# Schematic_Ej3_Amp_Instrumentacion.net
KiCad netlist of a schematic drawn in Altium Designer
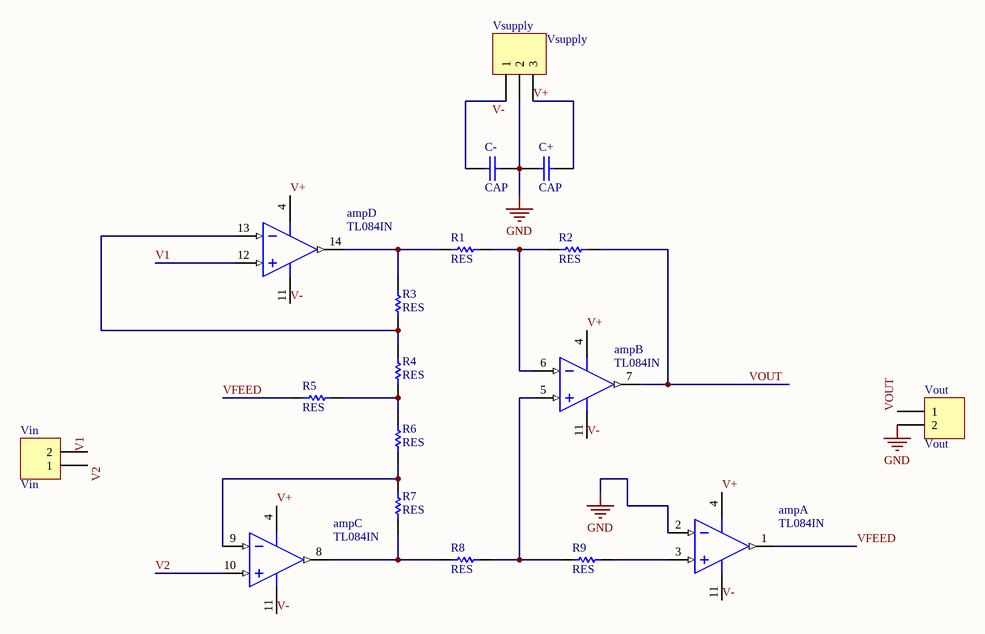
[diagram p0: Schematic_Ej3_Amp_Instrumentacion.SchDoc]

(export (version "E")
  (design (tool "Eeschema 10.0.6"))
  (components
    (comp (ref "amp")
      (value "TL084IN")
      (footprint "TI-N14")
      (description "JFET-Input Operational Amplifier, 7 to 36 V, -40 to 85 degC, 14-pin DIP (N14), Pb-Free (RoHS)")
      (fields (field (name "MANUFACTURER") "Texas Instruments"))
      (libsource (lib "TI Amplifiers and Linear Operational Amplifier General Purpose") (part "TL084IN"))
    )
    (comp (ref "C+") (value "CAP") (footprint "CAP200") (libsource (lib "LIBEBAL") (part "CAP")))
    (comp (ref "C-") (value "CAP") (footprint "CAP200") (libsource (lib "LIBEBAL") (part "CAP")))
    (comp (ref "R1") (value "RES") (footprint "0805") (libsource (lib "LIBEBAL") (part "RES")))
    (comp (ref "R2") (value "RES") (footprint "0805") (libsource (lib "LIBEBAL") (part "RES")))
    (comp (ref "R3") (value "RES") (footprint "0805") (libsource (lib "LIBEBAL") (part "RES")))
    (comp (ref "R4") (value "RES") (footprint "0805") (libsource (lib "LIBEBAL") (part "RES")))
    (comp (ref "R5") (value "RES") (footprint "0805") (libsource (lib "LIBEBAL") (part "RES")))
    (comp (ref "R6") (value "RES") (footprint "0805") (libsource (lib "LIBEBAL") (part "RES")))
    (comp (ref "R7") (value "RES") (footprint "0805") (libsource (lib "LIBEBAL") (part "RES")))
    (comp (ref "R8") (value "RES") (footprint "0805") (libsource (lib "LIBEBAL") (part "RES")))
    (comp (ref "R9") (value "RES") (footprint "0805") (libsource (lib "LIBEBAL") (part "RES")))
    (comp (ref "Vin")
      (value "Vin")
      (footprint "HDR1X2")
      (description "Header, 2-Pin")
      (fields (field (name "PUBLISHER") "Altium Limited"))
      (libsource (lib "") (part "Header 2_1"))
    )
    (comp (ref "Vout")
      (value "Vout")
      (footprint "HDR1X2")
      (description "Header, 2-Pin")
      (fields (field (name "PUBLISHER") "Altium Limited"))
      (libsource (lib "Miscellaneous Connectors") (part "Header 2"))
    )
    (comp (ref "Vsupply")
      (value "Vsupply")
      (footprint "HDR1X3")
      (description "Header, 3-Pin")
      (fields (field (name "PUBLISHER") "Altium Limited"))
      (libsource (lib "Miscellaneous Connectors") (part "Header 3"))
    )
  )
  (nets
    (net (code "1") (name "/V+") (class "Default")
      (node (ref "C+") (pin "2") (pinfunction "2_2") (pintype "passive"))
      (node (ref "Vsupply") (pin "3") (pinfunction "3_3") (pintype "passive"))
      (node (ref "amp") (pin "4") (pinfunction "VCC+_4") (pintype "power_in"))
    )
    (net (code "2") (name "/V-") (class "Default")
      (node (ref "C-") (pin "1") (pinfunction "1_1") (pintype "passive"))
      (node (ref "Vsupply") (pin "1") (pinfunction "1_1") (pintype "passive"))
      (node (ref "amp") (pin "11") (pinfunction "VCC-_11") (pintype "power_in"))
    )
    (net (code "3") (name "/V1") (class "Default")
      (node (ref "Vin") (pin "2") (pinfunction "2_2") (pintype "passive"))
      (node (ref "amp") (pin "12") (pinfunction "IN4+_12") (pintype "input"))
    )
    (net (code "4") (name "/V2") (class "Default")
      (node (ref "Vin") (pin "1") (pinfunction "1_1") (pintype "passive"))
      (node (ref "amp") (pin "10") (pinfunction "IN3+_10") (pintype "input"))
    )
    (net (code "5") (name "/VFEED") (class "Default")
      (node (ref "R5") (pin "1") (pinfunction "1_1") (pintype "passive"))
      (node (ref "amp") (pin "1") (pinfunction "OUT1_1") (pintype "output"))
    )
    (net (code "6") (name "/VOUT") (class "Default")
      (node (ref "R2") (pin "1") (pinfunction "1_1") (pintype "passive"))
      (node (ref "Vout") (pin "1") (pinfunction "1_1") (pintype "passive"))
      (node (ref "amp") (pin "7") (pinfunction "OUT2_7") (pintype "output"))
    )
    (net (code "7") (name "GND") (class "Default")
      (node (ref "C+") (pin "1") (pinfunction "1_1") (pintype "passive"))
      (node (ref "C-") (pin "2") (pinfunction "2_2") (pintype "passive"))
      (node (ref "Vout") (pin "2") (pinfunction "2_2") (pintype "passive"))
      (node (ref "Vsupply") (pin "2") (pinfunction "2_2") (pintype "passive"))
      (node (ref "amp") (pin "2") (pinfunction "IN1-_2") (pintype "input"))
    )
    (net (code "8") (name "Net-(R4-Pad1)") (class "Default")
      (node (ref "R4") (pin "1") (pinfunction "1_1") (pintype "passive"))
      (node (ref "R5") (pin "2") (pinfunction "2_2") (pintype "passive"))
      (node (ref "R6") (pin "1") (pinfunction "1_1") (pintype "passive"))
    )
    (net (code "9") (name "Net-(ampA-IN1+)") (class "Default")
      (node (ref "R9") (pin "2") (pinfunction "2_2") (pintype "passive"))
      (node (ref "amp") (pin "3") (pinfunction "IN1+_3") (pintype "input"))
    )
    (net (code "10") (name "Net-(ampB-IN2+)") (class "Default")
      (node (ref "R8") (pin "2") (pinfunction "2_2") (pintype "passive"))
      (node (ref "R9") (pin "1") (pinfunction "1_1") (pintype "passive"))
      (node (ref "amp") (pin "5") (pinfunction "IN2+_5") (pintype "input"))
    )
    (net (code "11") (name "Net-(ampB-IN2-)") (class "Default")
      (node (ref "R1") (pin "1") (pinfunction "1_1") (pintype "passive"))
      (node (ref "R2") (pin "2") (pinfunction "2_2") (pintype "passive"))
      (node (ref "amp") (pin "6") (pinfunction "IN2-_6") (pintype "input"))
    )
    (net (code "12") (name "Net-(ampC-IN3-)") (class "Default")
      (node (ref "R6") (pin "2") (pinfunction "2_2") (pintype "passive"))
      (node (ref "R7") (pin "2") (pinfunction "2_2") (pintype "passive"))
      (node (ref "amp") (pin "9") (pinfunction "IN3-_9") (pintype "input"))
    )
    (net (code "13") (name "Net-(ampC-OUT3)") (class "Default")
      (node (ref "R7") (pin "1") (pinfunction "1_1") (pintype "passive"))
      (node (ref "R8") (pin "1") (pinfunction "1_1") (pintype "passive"))
      (node (ref "amp") (pin "8") (pinfunction "OUT3_8") (pintype "output"))
    )
    (net (code "14") (name "Net-(ampD-IN4-)") (class "Default")
      (node (ref "R3") (pin "1") (pinfunction "1_1") (pintype "passive"))
      (node (ref "R4") (pin "2") (pinfunction "2_2") (pintype "passive"))
      (node (ref "amp") (pin "13") (pinfunction "IN4-_13") (pintype "input"))
    )
    (net (code "15") (name "Net-(ampD-OUT4)") (class "Default")
      (node (ref "R1") (pin "2") (pinfunction "2_2") (pintype "passive"))
      (node (ref "R3") (pin "2") (pinfunction "2_2") (pintype "passive"))
      (node (ref "amp") (pin "14") (pinfunction "OUT4_14") (pintype "output"))
    )
  )
)
